# RAM.net
KiCad netlist of a schematic drawn in Altium Designer
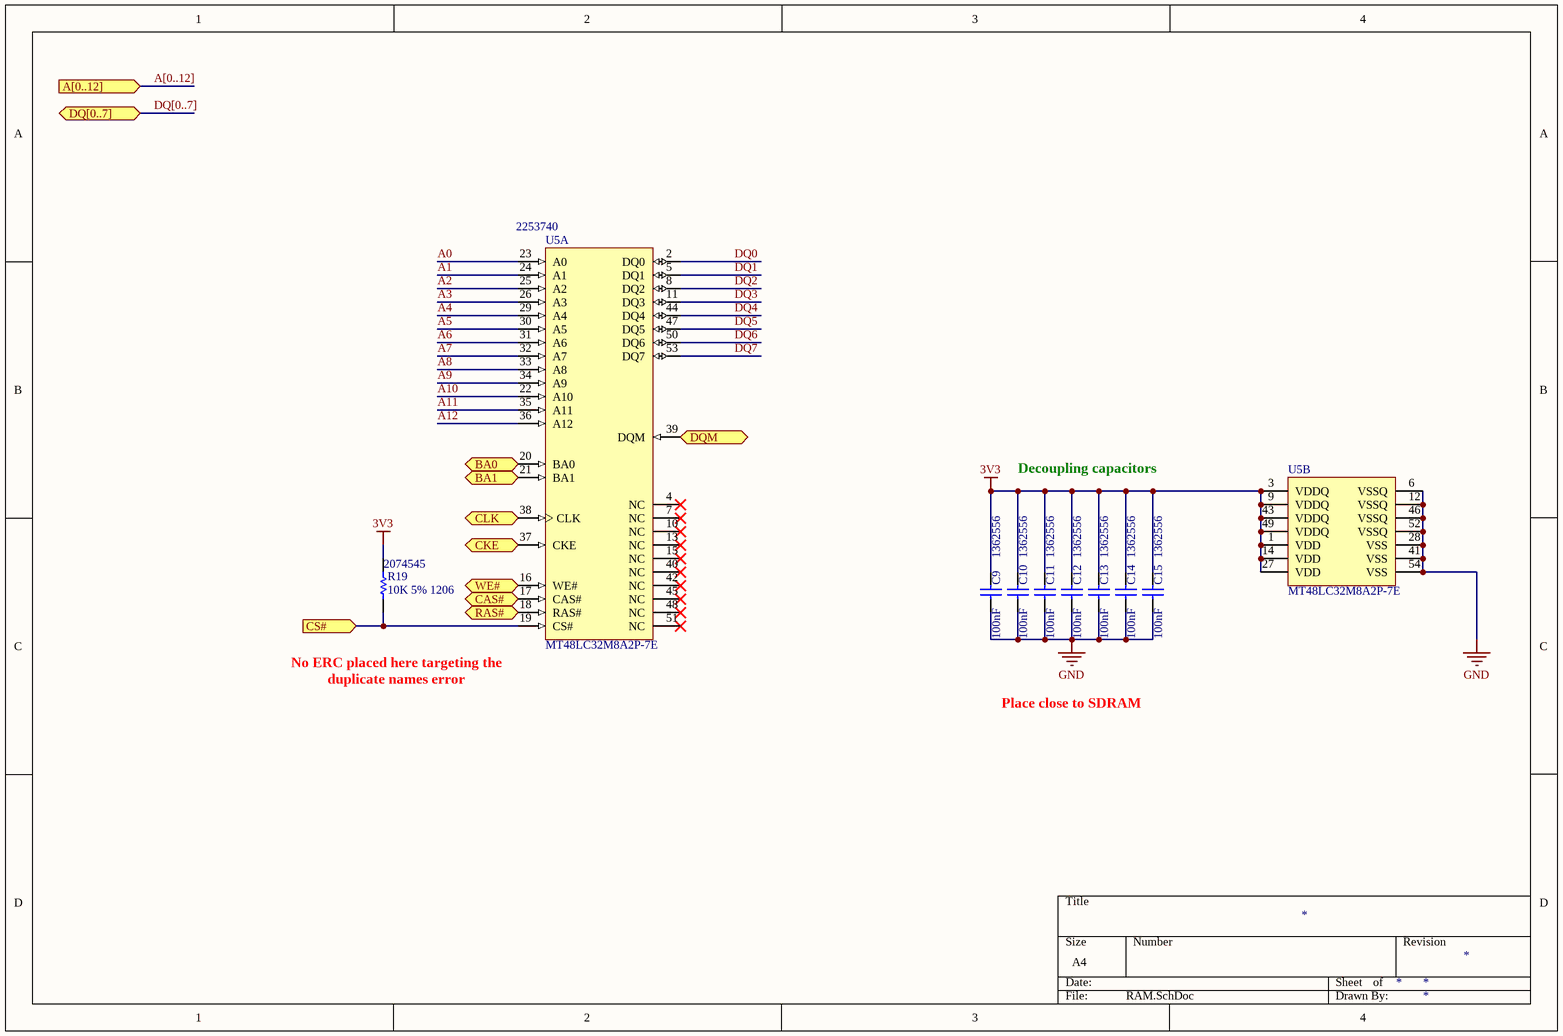
[diagram p0: RAM.SchDoc]

(export (version "E")
  (design (tool "Eeschema 10.0.6"))
  (components
    (comp (ref "C9")
      (value "100nF")
      (footprint "CAPC0603(1608)100_N")
      (description "CAP 100nF 50V ±10% 0603 (1608 Metric) Thickness 1mm SMD")
      (fields (field (name "TOLERANCE") "±10%") (field (name "SUPPLIER PART NUMBER 1") "1362556"))
      (libsource (lib "Altium Content Vault") (part "CMP-1035-02592-1"))
    )
    (comp (ref "C10")
      (value "100nF")
      (footprint "CAPC0603(1608)100_N")
      (description "CAP 100nF 50V ±10% 0603 (1608 Metric) Thickness 1mm SMD")
      (fields (field (name "TOLERANCE") "±10%") (field (name "SUPPLIER PART NUMBER 1") "1362556"))
      (libsource (lib "Altium Content Vault") (part "CMP-1035-02592-1"))
    )
    (comp (ref "C11")
      (value "100nF")
      (footprint "CAPC0603(1608)100_N")
      (description "CAP 100nF 50V ±10% 0603 (1608 Metric) Thickness 1mm SMD")
      (fields (field (name "TOLERANCE") "±10%") (field (name "SUPPLIER PART NUMBER 1") "1362556"))
      (libsource (lib "Altium Content Vault") (part "CMP-1035-02592-1"))
    )
    (comp (ref "C12")
      (value "100nF")
      (footprint "CAPC0603(1608)100_N")
      (description "CAP 100nF 50V ±10% 0603 (1608 Metric) Thickness 1mm SMD")
      (fields (field (name "TOLERANCE") "±10%") (field (name "SUPPLIER PART NUMBER 1") "1362556"))
      (libsource (lib "Altium Content Vault") (part "CMP-1035-02592-1"))
    )
    (comp (ref "C13")
      (value "100nF")
      (footprint "CAPC0603(1608)100_N")
      (description "CAP 100nF 50V ±10% 0603 (1608 Metric) Thickness 1mm SMD")
      (fields (field (name "TOLERANCE") "±10%") (field (name "SUPPLIER PART NUMBER 1") "1362556"))
      (libsource (lib "Altium Content Vault") (part "CMP-1035-02592-1"))
    )
    (comp (ref "C14")
      (value "100nF")
      (footprint "CAPC0603(1608)100_N")
      (description "CAP 100nF 50V ±10% 0603 (1608 Metric) Thickness 1mm SMD")
      (fields (field (name "TOLERANCE") "±10%") (field (name "SUPPLIER PART NUMBER 1") "1362556"))
      (libsource (lib "Altium Content Vault") (part "CMP-1035-02592-1"))
    )
    (comp (ref "C15")
      (value "100nF")
      (footprint "CAPC0603(1608)100_N")
      (description "CAP 100nF 50V ±10% 0603 (1608 Metric) Thickness 1mm SMD")
      (fields (field (name "TOLERANCE") "±10%") (field (name "SUPPLIER PART NUMBER 1") "1362556"))
      (libsource (lib "Altium Content Vault") (part "CMP-1035-02592-1"))
    )
    (comp (ref "R19")
      (value "10K 5% 1206")
      (footprint "RESC1206(3216)_M")
      (description "10K 0.25W 5% 1206 (3216 Metric)  SMD")
      (fields
        (field (name "POWER") "0.25 W")
        (field (name "TOLERANCE") "5 %")
        (field (name "SUPPLIER PART NUMBER 1") "2074545")
      )
      (libsource (lib "Altium Content Vault") (part "CMP-1014-00098-1"))
    )
    (comp (ref "U5")
      (value "MT48LC32M8A2P-7E")
      (footprint "MICT-P-54_N")
      (description "256Mb PC133 SDR SDRAM, 32Mb x 8, 7.5ns, 3.3V, 0 to 70 degC, 54-Pin TSOP, Pb-Free")
      (fields
        (field (name "VOLTAGE") "3.3V ")
        (field (name "MANUFACTURER") "Micron")
        (field (name "SUPPLIER PART NUMBER 1") "2253740")
      )
      (libsource (lib "Altium Content Vault") (part "MICT-MT48LC32M8A2P-54"))
    )
  )
  (nets
    (net (code "1") (name "/A0") (class "Default")
      (node (ref "U5") (pin "23") (pinfunction "A0_23") (pintype "input"))
    )
    (net (code "2") (name "/A1") (class "Default")
      (node (ref "U5") (pin "24") (pinfunction "A1_24") (pintype "input"))
    )
    (net (code "3") (name "/A2") (class "Default")
      (node (ref "U5") (pin "25") (pinfunction "A2_25") (pintype "input"))
    )
    (net (code "4") (name "/A3") (class "Default")
      (node (ref "U5") (pin "26") (pinfunction "A3_26") (pintype "input"))
    )
    (net (code "5") (name "/A4") (class "Default")
      (node (ref "U5") (pin "29") (pinfunction "A4_29") (pintype "input"))
    )
    (net (code "6") (name "/A5") (class "Default")
      (node (ref "U5") (pin "30") (pinfunction "A5_30") (pintype "input"))
    )
    (net (code "7") (name "/A6") (class "Default")
      (node (ref "U5") (pin "31") (pinfunction "A6_31") (pintype "input"))
    )
    (net (code "8") (name "/A7") (class "Default")
      (node (ref "U5") (pin "32") (pinfunction "A7_32") (pintype "input"))
    )
    (net (code "9") (name "/A8") (class "Default")
      (node (ref "U5") (pin "33") (pinfunction "A8_33") (pintype "input"))
    )
    (net (code "10") (name "/A9") (class "Default")
      (node (ref "U5") (pin "34") (pinfunction "A9_34") (pintype "input"))
    )
    (net (code "11") (name "/A10") (class "Default")
      (node (ref "U5") (pin "22") (pinfunction "A10_22") (pintype "input"))
    )
    (net (code "12") (name "/A11") (class "Default")
      (node (ref "U5") (pin "35") (pinfunction "A11_35") (pintype "input"))
    )
    (net (code "13") (name "/A12") (class "Default")
      (node (ref "U5") (pin "36") (pinfunction "A12_36") (pintype "input"))
    )
    (net (code "15") (name "/BA0") (class "Default")
      (node (ref "U5") (pin "20") (pinfunction "BA0_20") (pintype "input"))
    )
    (net (code "16") (name "/BA1") (class "Default")
      (node (ref "U5") (pin "21") (pinfunction "BA1_21") (pintype "input"))
    )
    (net (code "17") (name "/CAS#") (class "Default")
      (node (ref "U5") (pin "17") (pinfunction "CAS#_17") (pintype "input"))
    )
    (net (code "18") (name "/CKE") (class "Default")
      (node (ref "U5") (pin "37") (pinfunction "CKE_37") (pintype "input"))
    )
    (net (code "19") (name "/CLK") (class "Default")
      (node (ref "U5") (pin "38") (pinfunction "CLK_38") (pintype "input"))
    )
    (net (code "20") (name "/CS#") (class "Default")
      (node (ref "R19") (pin "1") (pinfunction "1_1") (pintype "passive"))
      (node (ref "U5") (pin "19") (pinfunction "CS#_19") (pintype "input"))
    )
    (net (code "21") (name "/DQ0") (class "Default")
      (node (ref "U5") (pin "2") (pinfunction "DQ0_2") (pintype "bidirectional"))
    )
    (net (code "22") (name "/DQ1") (class "Default")
      (node (ref "U5") (pin "5") (pinfunction "DQ1_5") (pintype "bidirectional"))
    )
    (net (code "23") (name "/DQ2") (class "Default")
      (node (ref "U5") (pin "8") (pinfunction "DQ2_8") (pintype "bidirectional"))
    )
    (net (code "24") (name "/DQ3") (class "Default")
      (node (ref "U5") (pin "11") (pinfunction "DQ3_11") (pintype "bidirectional"))
    )
    (net (code "25") (name "/DQ4") (class "Default")
      (node (ref "U5") (pin "44") (pinfunction "DQ4_44") (pintype "bidirectional"))
    )
    (net (code "26") (name "/DQ5") (class "Default")
      (node (ref "U5") (pin "47") (pinfunction "DQ5_47") (pintype "bidirectional"))
    )
    (net (code "27") (name "/DQ6") (class "Default")
      (node (ref "U5") (pin "50") (pinfunction "DQ6_50") (pintype "bidirectional"))
    )
    (net (code "28") (name "/DQ7") (class "Default")
      (node (ref "U5") (pin "53") (pinfunction "DQ7_53") (pintype "bidirectional"))
    )
    (net (code "29") (name "/DQM") (class "Default")
      (node (ref "U5") (pin "39") (pinfunction "DQM_39") (pintype "input"))
    )
    (net (code "31") (name "/RAS#") (class "Default")
      (node (ref "U5") (pin "18") (pinfunction "RAS#_18") (pintype "input"))
    )
    (net (code "32") (name "/WE#") (class "Default")
      (node (ref "U5") (pin "16") (pinfunction "WE#_16") (pintype "input"))
    )
    (net (code "33") (name "3V3") (class "Default")
      (node (ref "C10") (pin "2") (pinfunction "2_2") (pintype "passive"))
      (node (ref "C11") (pin "2") (pinfunction "2_2") (pintype "passive"))
      (node (ref "C12") (pin "2") (pinfunction "2_2") (pintype "passive"))
      (node (ref "C13") (pin "2") (pinfunction "2_2") (pintype "passive"))
      (node (ref "C14") (pin "2") (pinfunction "2_2") (pintype "passive"))
      (node (ref "C15") (pin "2") (pinfunction "2_2") (pintype "passive"))
      (node (ref "C9") (pin "2") (pinfunction "2_2") (pintype "passive"))
      (node (ref "R19") (pin "2") (pinfunction "2_2") (pintype "passive"))
      (node (ref "U5") (pin "1") (pinfunction "VDD_1") (pintype "power_in"))
      (node (ref "U5") (pin "14") (pinfunction "VDD_14") (pintype "power_in"))
      (node (ref "U5") (pin "27") (pinfunction "VDD_27") (pintype "power_in"))
      (node (ref "U5") (pin "3") (pinfunction "VDDQ_3") (pintype "power_in"))
      (node (ref "U5") (pin "43") (pinfunction "VDDQ_43") (pintype "power_in"))
      (node (ref "U5") (pin "49") (pinfunction "VDDQ_49") (pintype "power_in"))
      (node (ref "U5") (pin "9") (pinfunction "VDDQ_9") (pintype "power_in"))
    )
    (net (code "34") (name "GND") (class "Default")
      (node (ref "C10") (pin "1") (pinfunction "1_1") (pintype "passive"))
      (node (ref "C11") (pin "1") (pinfunction "1_1") (pintype "passive"))
      (node (ref "C12") (pin "1") (pinfunction "1_1") (pintype "passive"))
      (node (ref "C13") (pin "1") (pinfunction "1_1") (pintype "passive"))
      (node (ref "C14") (pin "1") (pinfunction "1_1") (pintype "passive"))
      (node (ref "C15") (pin "1") (pinfunction "1_1") (pintype "passive"))
      (node (ref "C9") (pin "1") (pinfunction "1_1") (pintype "passive"))
      (node (ref "U5") (pin "12") (pinfunction "VSSQ_12") (pintype "power_in"))
      (node (ref "U5") (pin "28") (pinfunction "VSS_28") (pintype "power_in"))
      (node (ref "U5") (pin "41") (pinfunction "VSS_41") (pintype "power_in"))
      (node (ref "U5") (pin "46") (pinfunction "VSSQ_46") (pintype "power_in"))
      (node (ref "U5") (pin "52") (pinfunction "VSSQ_52") (pintype "power_in"))
      (node (ref "U5") (pin "54") (pinfunction "VSS_54") (pintype "power_in"))
      (node (ref "U5") (pin "6") (pinfunction "VSSQ_6") (pintype "power_in"))
    )
    (net (code "35") (name "unconnected-(U5A-NC-Pad4)") (class "Default")
      (node (ref "U5") (pin "4") (pinfunction "NC_4") (pintype "passive+no_connect"))
    )
    (net (code "36") (name "unconnected-(U5A-NC-Pad7)") (class "Default")
      (node (ref "U5") (pin "7") (pinfunction "NC_7") (pintype "passive+no_connect"))
    )
    (net (code "37") (name "unconnected-(U5A-NC-Pad10)") (class "Default")
      (node (ref "U5") (pin "10") (pinfunction "NC_10") (pintype "passive+no_connect"))
    )
    (net (code "38") (name "unconnected-(U5A-NC-Pad13)") (class "Default")
      (node (ref "U5") (pin "13") (pinfunction "NC_13") (pintype "passive+no_connect"))
    )
    (net (code "39") (name "unconnected-(U5A-NC-Pad15)") (class "Default")
      (node (ref "U5") (pin "15") (pinfunction "NC_15") (pintype "passive+no_connect"))
    )
    (net (code "40") (name "unconnected-(U5A-NC-Pad40)") (class "Default")
      (node (ref "U5") (pin "40") (pinfunction "NC_40") (pintype "passive+no_connect"))
    )
    (net (code "41") (name "unconnected-(U5A-NC-Pad42)") (class "Default")
      (node (ref "U5") (pin "42") (pinfunction "NC_42") (pintype "passive+no_connect"))
    )
    (net (code "42") (name "unconnected-(U5A-NC-Pad45)") (class "Default")
      (node (ref "U5") (pin "45") (pinfunction "NC_45") (pintype "passive+no_connect"))
    )
    (net (code "43") (name "unconnected-(U5A-NC-Pad48)") (class "Default")
      (node (ref "U5") (pin "48") (pinfunction "NC_48") (pintype "passive+no_connect"))
    )
    (net (code "44") (name "unconnected-(U5A-NC-Pad51)") (class "Default")
      (node (ref "U5") (pin "51") (pinfunction "NC_51") (pintype "passive+no_connect"))
    )
  )
)
